# Sheet1.net
KiCad netlist of a schematic drawn in Altium Designer
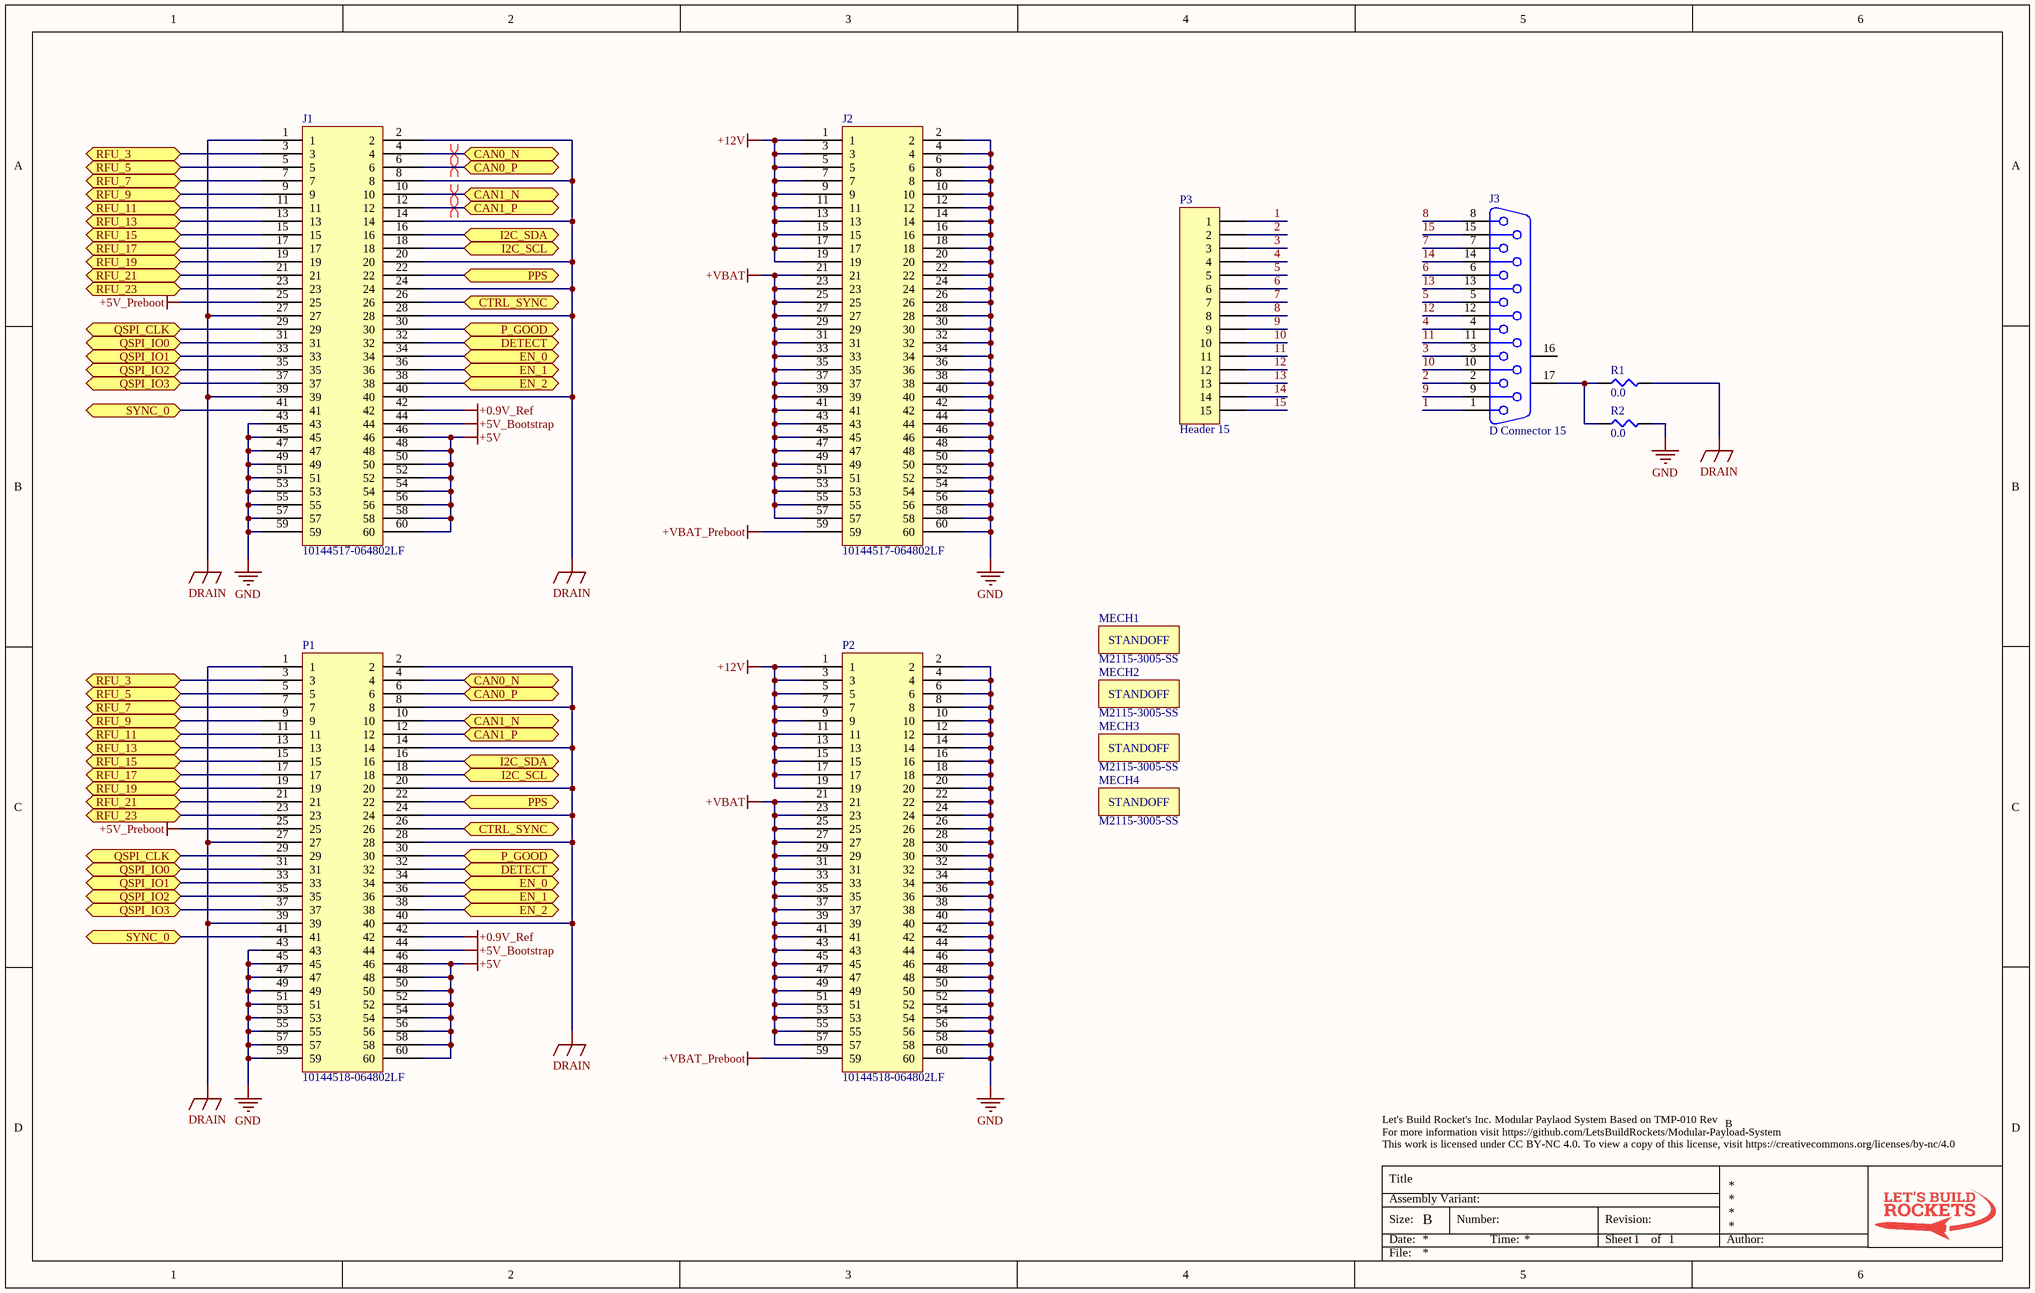
[diagram p0: Sheet1.SchDoc]

(export (version "E")
  (design (tool "Eeschema 10.0.6"))
  (components
    (comp (ref "J1")
      (value "10144517-064802LF")
      (footprint "10144517-064802LF")
      (libsource (lib "ModularPayload") (part "10144517-064802LF"))
    )
    (comp (ref "J2")
      (value "10144517-064802LF")
      (footprint "10144517-064802LF")
      (libsource (lib "ModularPayload") (part "10144517-064802LF"))
    )
    (comp (ref "J3")
      (value "D Connector 15")
      (footprint "DSUB1.385-2H15")
      (description "Receptacle Assembly, 15 Position, Right Angle")
      (fields (field (name "PUBLISHER") "Altium Limited"))
      (libsource (lib "Miscellaneous Connectors") (part "D Connector 15"))
    )
    (comp (ref "MECH1")
      (value "M2115-3005-SS")
      (footprint "M2115-3005-SS")
      (libsource (lib "ModularPayload") (part "M2115-3005-SS"))
    )
    (comp (ref "MECH2")
      (value "M2115-3005-SS")
      (footprint "M2115-3005-SS")
      (libsource (lib "ModularPayload") (part "M2115-3005-SS"))
    )
    (comp (ref "MECH3")
      (value "M2115-3005-SS")
      (footprint "M2115-3005-SS")
      (libsource (lib "ModularPayload") (part "M2115-3005-SS"))
    )
    (comp (ref "MECH4")
      (value "M2115-3005-SS")
      (footprint "M2115-3005-SS")
      (libsource (lib "ModularPayload") (part "M2115-3005-SS"))
    )
    (comp (ref "P1")
      (value "10144518-064802LF")
      (footprint "10144518-064802LF")
      (libsource (lib "ModularPayload") (part "10144518-064802LF"))
    )
    (comp (ref "P2")
      (value "10144518-064802LF")
      (footprint "10144518-064802LF")
      (libsource (lib "ModularPayload") (part "10144518-064802LF"))
    )
    (comp (ref "P3")
      (value "Header 15")
      (footprint "HDR1X15")
      (description "Header, 15-Pin")
      (fields (field (name "PUBLISHER") "Altium Limited"))
      (libsource (lib "Miscellaneous Connectors") (part "Header 15"))
    )
    (comp (ref "R1")
      (value "0.0")
      (footprint "SMD-0402-RES")
      (description "RES SMD 0.0OHM JUMPER 1/10W 0402")
      (fields (field (name "PART NUMBER") "ERJ-2GE0R00X") (field (name "DIGI-KEY PART NUMBER") "P0.0JCT-ND"))
      (libsource (lib "Panasonic_ERJ_0402") (part "ERJ-2GE0R00X"))
    )
    (comp (ref "R2")
      (value "0.0")
      (footprint "SMD-0402-RES")
      (description "RES SMD 0.0OHM JUMPER 1/10W 0402")
      (fields (field (name "PART NUMBER") "ERJ-2GE0R00X") (field (name "DIGI-KEY PART NUMBER") "P0.0JCT-ND"))
      (libsource (lib "Panasonic_ERJ_0402") (part "ERJ-2GE0R00X"))
    )
  )
  (nets
    (net (code "1") (name "+0.9V_Ref") (class "Default")
      (node (ref "J1") (pin "42") (pinfunction "42_42") (pintype "passive"))
      (node (ref "P1") (pin "42") (pinfunction "42_42") (pintype "passive"))
    )
    (net (code "2") (name "+5V") (class "Default")
      (node (ref "J1") (pin "46") (pinfunction "46_46") (pintype "passive"))
      (node (ref "J1") (pin "48") (pinfunction "48_48") (pintype "passive"))
      (node (ref "J1") (pin "50") (pinfunction "50_50") (pintype "passive"))
      (node (ref "J1") (pin "52") (pinfunction "52_52") (pintype "passive"))
      (node (ref "J1") (pin "54") (pinfunction "54_54") (pintype "passive"))
      (node (ref "J1") (pin "56") (pinfunction "56_56") (pintype "passive"))
      (node (ref "J1") (pin "58") (pinfunction "58_58") (pintype "passive"))
      (node (ref "J1") (pin "60") (pinfunction "60_60") (pintype "passive"))
      (node (ref "P1") (pin "46") (pinfunction "46_46") (pintype "passive"))
      (node (ref "P1") (pin "48") (pinfunction "48_48") (pintype "passive"))
      (node (ref "P1") (pin "50") (pinfunction "50_50") (pintype "passive"))
      (node (ref "P1") (pin "52") (pinfunction "52_52") (pintype "passive"))
      (node (ref "P1") (pin "54") (pinfunction "54_54") (pintype "passive"))
      (node (ref "P1") (pin "56") (pinfunction "56_56") (pintype "passive"))
      (node (ref "P1") (pin "58") (pinfunction "58_58") (pintype "passive"))
      (node (ref "P1") (pin "60") (pinfunction "60_60") (pintype "passive"))
    )
    (net (code "3") (name "+5V_Bootstrap") (class "Default")
      (node (ref "J1") (pin "44") (pinfunction "44_44") (pintype "passive"))
      (node (ref "P1") (pin "44") (pinfunction "44_44") (pintype "passive"))
    )
    (net (code "4") (name "+5V_Preboot") (class "Default")
      (node (ref "J1") (pin "25") (pinfunction "25_25") (pintype "passive"))
      (node (ref "P1") (pin "25") (pinfunction "25_25") (pintype "passive"))
    )
    (net (code "5") (name "+12V") (class "Default")
      (node (ref "J2") (pin "1") (pinfunction "1_1") (pintype "passive"))
      (node (ref "J2") (pin "11") (pinfunction "11_11") (pintype "passive"))
      (node (ref "J2") (pin "13") (pinfunction "13_13") (pintype "passive"))
      (node (ref "J2") (pin "15") (pinfunction "15_15") (pintype "passive"))
      (node (ref "J2") (pin "17") (pinfunction "17_17") (pintype "passive"))
      (node (ref "J2") (pin "19") (pinfunction "19_19") (pintype "passive"))
      (node (ref "J2") (pin "3") (pinfunction "3_3") (pintype "passive"))
      (node (ref "J2") (pin "5") (pinfunction "5_5") (pintype "passive"))
      (node (ref "J2") (pin "7") (pinfunction "7_7") (pintype "passive"))
      (node (ref "J2") (pin "9") (pinfunction "9_9") (pintype "passive"))
      (node (ref "P2") (pin "1") (pinfunction "1_1") (pintype "passive"))
      (node (ref "P2") (pin "11") (pinfunction "11_11") (pintype "passive"))
      (node (ref "P2") (pin "13") (pinfunction "13_13") (pintype "passive"))
      (node (ref "P2") (pin "15") (pinfunction "15_15") (pintype "passive"))
      (node (ref "P2") (pin "17") (pinfunction "17_17") (pintype "passive"))
      (node (ref "P2") (pin "19") (pinfunction "19_19") (pintype "passive"))
      (node (ref "P2") (pin "3") (pinfunction "3_3") (pintype "passive"))
      (node (ref "P2") (pin "5") (pinfunction "5_5") (pintype "passive"))
      (node (ref "P2") (pin "7") (pinfunction "7_7") (pintype "passive"))
      (node (ref "P2") (pin "9") (pinfunction "9_9") (pintype "passive"))
    )
    (net (code "6") (name "+VBAT") (class "Default")
      (node (ref "J2") (pin "21") (pinfunction "21_21") (pintype "passive"))
      (node (ref "J2") (pin "23") (pinfunction "23_23") (pintype "passive"))
      (node (ref "J2") (pin "25") (pinfunction "25_25") (pintype "passive"))
      (node (ref "J2") (pin "27") (pinfunction "27_27") (pintype "passive"))
      (node (ref "J2") (pin "29") (pinfunction "29_29") (pintype "passive"))
      (node (ref "J2") (pin "31") (pinfunction "31_31") (pintype "passive"))
      (node (ref "J2") (pin "33") (pinfunction "33_33") (pintype "passive"))
      (node (ref "J2") (pin "35") (pinfunction "35_35") (pintype "passive"))
      (node (ref "J2") (pin "37") (pinfunction "37_37") (pintype "passive"))
      (node (ref "J2") (pin "39") (pinfunction "39_39") (pintype "passive"))
      (node (ref "J2") (pin "41") (pinfunction "41_41") (pintype "passive"))
      (node (ref "J2") (pin "43") (pinfunction "43_43") (pintype "passive"))
      (node (ref "J2") (pin "45") (pinfunction "45_45") (pintype "passive"))
      (node (ref "J2") (pin "47") (pinfunction "47_47") (pintype "passive"))
      (node (ref "J2") (pin "49") (pinfunction "49_49") (pintype "passive"))
      (node (ref "J2") (pin "51") (pinfunction "51_51") (pintype "passive"))
      (node (ref "J2") (pin "53") (pinfunction "53_53") (pintype "passive"))
      (node (ref "J2") (pin "55") (pinfunction "55_55") (pintype "passive"))
      (node (ref "J2") (pin "57") (pinfunction "57_57") (pintype "passive"))
      (node (ref "P2") (pin "21") (pinfunction "21_21") (pintype "passive"))
      (node (ref "P2") (pin "23") (pinfunction "23_23") (pintype "passive"))
      (node (ref "P2") (pin "25") (pinfunction "25_25") (pintype "passive"))
      (node (ref "P2") (pin "27") (pinfunction "27_27") (pintype "passive"))
      (node (ref "P2") (pin "29") (pinfunction "29_29") (pintype "passive"))
      (node (ref "P2") (pin "31") (pinfunction "31_31") (pintype "passive"))
      (node (ref "P2") (pin "33") (pinfunction "33_33") (pintype "passive"))
      (node (ref "P2") (pin "35") (pinfunction "35_35") (pintype "passive"))
      (node (ref "P2") (pin "37") (pinfunction "37_37") (pintype "passive"))
      (node (ref "P2") (pin "39") (pinfunction "39_39") (pintype "passive"))
      (node (ref "P2") (pin "41") (pinfunction "41_41") (pintype "passive"))
      (node (ref "P2") (pin "43") (pinfunction "43_43") (pintype "passive"))
      (node (ref "P2") (pin "45") (pinfunction "45_45") (pintype "passive"))
      (node (ref "P2") (pin "47") (pinfunction "47_47") (pintype "passive"))
      (node (ref "P2") (pin "49") (pinfunction "49_49") (pintype "passive"))
      (node (ref "P2") (pin "51") (pinfunction "51_51") (pintype "passive"))
      (node (ref "P2") (pin "53") (pinfunction "53_53") (pintype "passive"))
      (node (ref "P2") (pin "55") (pinfunction "55_55") (pintype "passive"))
      (node (ref "P2") (pin "57") (pinfunction "57_57") (pintype "passive"))
    )
    (net (code "7") (name "+VBAT_Preboot") (class "Default")
      (node (ref "J2") (pin "59") (pinfunction "59_59") (pintype "passive"))
      (node (ref "P2") (pin "59") (pinfunction "59_59") (pintype "passive"))
    )
    (net (code "8") (name "/1") (class "Default")
      (node (ref "J3") (pin "1") (pinfunction "1_1") (pintype "passive"))
      (node (ref "P3") (pin "1") (pinfunction "1_1") (pintype "passive"))
    )
    (net (code "9") (name "/2") (class "Default")
      (node (ref "J3") (pin "2") (pinfunction "2_2") (pintype "passive"))
      (node (ref "P3") (pin "2") (pinfunction "2_2") (pintype "passive"))
    )
    (net (code "10") (name "/3") (class "Default")
      (node (ref "J3") (pin "3") (pinfunction "3_3") (pintype "passive"))
      (node (ref "P3") (pin "3") (pinfunction "3_3") (pintype "passive"))
    )
    (net (code "11") (name "/4") (class "Default")
      (node (ref "J3") (pin "4") (pinfunction "4_4") (pintype "passive"))
      (node (ref "P3") (pin "4") (pinfunction "4_4") (pintype "passive"))
    )
    (net (code "12") (name "/5") (class "Default")
      (node (ref "J3") (pin "5") (pinfunction "5_5") (pintype "passive"))
      (node (ref "P3") (pin "5") (pinfunction "5_5") (pintype "passive"))
    )
    (net (code "13") (name "/6") (class "Default")
      (node (ref "J3") (pin "6") (pinfunction "6_6") (pintype "passive"))
      (node (ref "P3") (pin "6") (pinfunction "6_6") (pintype "passive"))
    )
    (net (code "14") (name "/7") (class "Default")
      (node (ref "J3") (pin "7") (pinfunction "7_7") (pintype "passive"))
      (node (ref "P3") (pin "7") (pinfunction "7_7") (pintype "passive"))
    )
    (net (code "15") (name "/8") (class "Default")
      (node (ref "J3") (pin "8") (pinfunction "8_8") (pintype "passive"))
      (node (ref "P3") (pin "8") (pinfunction "8_8") (pintype "passive"))
    )
    (net (code "16") (name "/9") (class "Default")
      (node (ref "J3") (pin "9") (pinfunction "9_9") (pintype "passive"))
      (node (ref "P3") (pin "9") (pinfunction "9_9") (pintype "passive"))
    )
    (net (code "17") (name "/10") (class "Default")
      (node (ref "J3") (pin "10") (pinfunction "10_10") (pintype "passive"))
      (node (ref "P3") (pin "10") (pinfunction "10_10") (pintype "passive"))
    )
    (net (code "18") (name "/11") (class "Default")
      (node (ref "J3") (pin "11") (pinfunction "11_11") (pintype "passive"))
      (node (ref "P3") (pin "11") (pinfunction "11_11") (pintype "passive"))
    )
    (net (code "19") (name "/12") (class "Default")
      (node (ref "J3") (pin "12") (pinfunction "12_12") (pintype "passive"))
      (node (ref "P3") (pin "12") (pinfunction "12_12") (pintype "passive"))
    )
    (net (code "20") (name "/13") (class "Default")
      (node (ref "J3") (pin "13") (pinfunction "13_13") (pintype "passive"))
      (node (ref "P3") (pin "13") (pinfunction "13_13") (pintype "passive"))
    )
    (net (code "21") (name "/14") (class "Default")
      (node (ref "J3") (pin "14") (pinfunction "14_14") (pintype "passive"))
      (node (ref "P3") (pin "14") (pinfunction "14_14") (pintype "passive"))
    )
    (net (code "22") (name "/15") (class "Default")
      (node (ref "J3") (pin "15") (pinfunction "15_15") (pintype "passive"))
      (node (ref "P3") (pin "15") (pinfunction "15_15") (pintype "passive"))
    )
    (net (code "23") (name "/CAN0_N") (class "Default")
      (node (ref "J1") (pin "4") (pinfunction "4_4") (pintype "passive"))
      (node (ref "P1") (pin "4") (pinfunction "4_4") (pintype "passive"))
    )
    (net (code "24") (name "/CAN0_P") (class "Default")
      (node (ref "J1") (pin "6") (pinfunction "6_6") (pintype "passive"))
      (node (ref "P1") (pin "6") (pinfunction "6_6") (pintype "passive"))
    )
    (net (code "25") (name "/CAN1_N") (class "Default")
      (node (ref "J1") (pin "10") (pinfunction "10_10") (pintype "passive"))
      (node (ref "P1") (pin "10") (pinfunction "10_10") (pintype "passive"))
    )
    (net (code "26") (name "/CAN1_P") (class "Default")
      (node (ref "J1") (pin "12") (pinfunction "12_12") (pintype "passive"))
      (node (ref "P1") (pin "12") (pinfunction "12_12") (pintype "passive"))
    )
    (net (code "27") (name "/CTRL_SYNC") (class "Default")
      (node (ref "J1") (pin "26") (pinfunction "26_26") (pintype "passive"))
      (node (ref "P1") (pin "26") (pinfunction "26_26") (pintype "passive"))
    )
    (net (code "28") (name "/DETECT") (class "Default")
      (node (ref "J1") (pin "32") (pinfunction "32_32") (pintype "passive"))
      (node (ref "P1") (pin "32") (pinfunction "32_32") (pintype "passive"))
    )
    (net (code "29") (name "/EN_0") (class "Default")
      (node (ref "J1") (pin "34") (pinfunction "34_34") (pintype "passive"))
      (node (ref "P1") (pin "34") (pinfunction "34_34") (pintype "passive"))
    )
    (net (code "30") (name "/EN_1") (class "Default")
      (node (ref "J1") (pin "36") (pinfunction "36_36") (pintype "passive"))
      (node (ref "P1") (pin "36") (pinfunction "36_36") (pintype "passive"))
    )
    (net (code "31") (name "/EN_2") (class "Default")
      (node (ref "J1") (pin "38") (pinfunction "38_38") (pintype "passive"))
      (node (ref "P1") (pin "38") (pinfunction "38_38") (pintype "passive"))
    )
    (net (code "32") (name "/I2C_SCL") (class "Default")
      (node (ref "J1") (pin "18") (pinfunction "18_18") (pintype "passive"))
      (node (ref "P1") (pin "18") (pinfunction "18_18") (pintype "passive"))
    )
    (net (code "33") (name "/I2C_SDA") (class "Default")
      (node (ref "J1") (pin "16") (pinfunction "16_16") (pintype "passive"))
      (node (ref "P1") (pin "16") (pinfunction "16_16") (pintype "passive"))
    )
    (net (code "34") (name "/PPS") (class "Default")
      (node (ref "J1") (pin "22") (pinfunction "22_22") (pintype "passive"))
      (node (ref "P1") (pin "22") (pinfunction "22_22") (pintype "passive"))
    )
    (net (code "35") (name "/P_GOOD") (class "Default")
      (node (ref "J1") (pin "30") (pinfunction "30_30") (pintype "passive"))
      (node (ref "P1") (pin "30") (pinfunction "30_30") (pintype "passive"))
    )
    (net (code "36") (name "/QSPI_CLK") (class "Default")
      (node (ref "J1") (pin "29") (pinfunction "29_29") (pintype "passive"))
      (node (ref "P1") (pin "29") (pinfunction "29_29") (pintype "passive"))
    )
    (net (code "37") (name "/QSPI_IO0") (class "Default")
      (node (ref "J1") (pin "31") (pinfunction "31_31") (pintype "passive"))
      (node (ref "P1") (pin "31") (pinfunction "31_31") (pintype "passive"))
    )
    (net (code "38") (name "/QSPI_IO1") (class "Default")
      (node (ref "J1") (pin "33") (pinfunction "33_33") (pintype "passive"))
      (node (ref "P1") (pin "33") (pinfunction "33_33") (pintype "passive"))
    )
    (net (code "39") (name "/QSPI_IO2") (class "Default")
      (node (ref "J1") (pin "35") (pinfunction "35_35") (pintype "passive"))
      (node (ref "P1") (pin "35") (pinfunction "35_35") (pintype "passive"))
    )
    (net (code "40") (name "/QSPI_IO3") (class "Default")
      (node (ref "J1") (pin "37") (pinfunction "37_37") (pintype "passive"))
      (node (ref "P1") (pin "37") (pinfunction "37_37") (pintype "passive"))
    )
    (net (code "41") (name "/RFU_3") (class "Default")
      (node (ref "J1") (pin "3") (pinfunction "3_3") (pintype "passive"))
      (node (ref "P1") (pin "3") (pinfunction "3_3") (pintype "passive"))
    )
    (net (code "42") (name "/RFU_5") (class "Default")
      (node (ref "J1") (pin "5") (pinfunction "5_5") (pintype "passive"))
      (node (ref "P1") (pin "5") (pinfunction "5_5") (pintype "passive"))
    )
    (net (code "43") (name "/RFU_7") (class "Default")
      (node (ref "J1") (pin "7") (pinfunction "7_7") (pintype "passive"))
      (node (ref "P1") (pin "7") (pinfunction "7_7") (pintype "passive"))
    )
    (net (code "44") (name "/RFU_9") (class "Default")
      (node (ref "J1") (pin "9") (pinfunction "9_9") (pintype "passive"))
      (node (ref "P1") (pin "9") (pinfunction "9_9") (pintype "passive"))
    )
    (net (code "45") (name "/RFU_11") (class "Default")
      (node (ref "J1") (pin "11") (pinfunction "11_11") (pintype "passive"))
      (node (ref "P1") (pin "11") (pinfunction "11_11") (pintype "passive"))
    )
    (net (code "46") (name "/RFU_13") (class "Default")
      (node (ref "J1") (pin "13") (pinfunction "13_13") (pintype "passive"))
      (node (ref "P1") (pin "13") (pinfunction "13_13") (pintype "passive"))
    )
    (net (code "47") (name "/RFU_15") (class "Default")
      (node (ref "J1") (pin "15") (pinfunction "15_15") (pintype "passive"))
      (node (ref "P1") (pin "15") (pinfunction "15_15") (pintype "passive"))
    )
    (net (code "48") (name "/RFU_17") (class "Default")
      (node (ref "J1") (pin "17") (pinfunction "17_17") (pintype "passive"))
      (node (ref "P1") (pin "17") (pinfunction "17_17") (pintype "passive"))
    )
    (net (code "49") (name "/RFU_19") (class "Default")
      (node (ref "J1") (pin "19") (pinfunction "19_19") (pintype "passive"))
      (node (ref "P1") (pin "19") (pinfunction "19_19") (pintype "passive"))
    )
    (net (code "50") (name "/RFU_21") (class "Default")
      (node (ref "J1") (pin "21") (pinfunction "21_21") (pintype "passive"))
      (node (ref "P1") (pin "21") (pinfunction "21_21") (pintype "passive"))
    )
    (net (code "51") (name "/RFU_23") (class "Default")
      (node (ref "J1") (pin "23") (pinfunction "23_23") (pintype "passive"))
      (node (ref "P1") (pin "23") (pinfunction "23_23") (pintype "passive"))
    )
    (net (code "52") (name "/SYNC_0") (class "Default")
      (node (ref "J1") (pin "41") (pinfunction "41_41") (pintype "passive"))
      (node (ref "P1") (pin "41") (pinfunction "41_41") (pintype "passive"))
    )
    (net (code "53") (name "DRAIN") (class "Default")
      (node (ref "J1") (pin "1") (pinfunction "1_1") (pintype "passive"))
      (node (ref "J1") (pin "14") (pinfunction "14_14") (pintype "passive"))
      (node (ref "J1") (pin "2") (pinfunction "2_2") (pintype "passive"))
      (node (ref "J1") (pin "20") (pinfunction "20_20") (pintype "passive"))
      (node (ref "J1") (pin "24") (pinfunction "24_24") (pintype "passive"))
      (node (ref "J1") (pin "27") (pinfunction "27_27") (pintype "passive"))
      (node (ref "J1") (pin "28") (pinfunction "28_28") (pintype "passive"))
      (node (ref "J1") (pin "39") (pinfunction "39_39") (pintype "passive"))
      (node (ref "J1") (pin "40") (pinfunction "40_40") (pintype "passive"))
      (node (ref "J1") (pin "8") (pinfunction "8_8") (pintype "passive"))
      (node (ref "P1") (pin "1") (pinfunction "1_1") (pintype "passive"))
      (node (ref "P1") (pin "14") (pinfunction "14_14") (pintype "passive"))
      (node (ref "P1") (pin "2") (pinfunction "2_2") (pintype "passive"))
      (node (ref "P1") (pin "20") (pinfunction "20_20") (pintype "passive"))
      (node (ref "P1") (pin "24") (pinfunction "24_24") (pintype "passive"))
      (node (ref "P1") (pin "27") (pinfunction "27_27") (pintype "passive"))
      (node (ref "P1") (pin "28") (pinfunction "28_28") (pintype "passive"))
      (node (ref "P1") (pin "39") (pinfunction "39_39") (pintype "passive"))
      (node (ref "P1") (pin "40") (pinfunction "40_40") (pintype "passive"))
      (node (ref "P1") (pin "8") (pinfunction "8_8") (pintype "passive"))
      (node (ref "R1") (pin "2") (pinfunction "2_2") (pintype "passive"))
    )
    (net (code "54") (name "GND") (class "Default")
      (node (ref "J1") (pin "43") (pinfunction "43_43") (pintype "passive"))
      (node (ref "J1") (pin "45") (pinfunction "45_45") (pintype "passive"))
      (node (ref "J1") (pin "47") (pinfunction "47_47") (pintype "passive"))
      (node (ref "J1") (pin "49") (pinfunction "49_49") (pintype "passive"))
      (node (ref "J1") (pin "51") (pinfunction "51_51") (pintype "passive"))
      (node (ref "J1") (pin "53") (pinfunction "53_53") (pintype "passive"))
      (node (ref "J1") (pin "55") (pinfunction "55_55") (pintype "passive"))
      (node (ref "J1") (pin "57") (pinfunction "57_57") (pintype "passive"))
      (node (ref "J1") (pin "59") (pinfunction "59_59") (pintype "passive"))
      (node (ref "J2") (pin "10") (pinfunction "10_10") (pintype "passive"))
      (node (ref "J2") (pin "12") (pinfunction "12_12") (pintype "passive"))
      (node (ref "J2") (pin "14") (pinfunction "14_14") (pintype "passive"))
      (node (ref "J2") (pin "16") (pinfunction "16_16") (pintype "passive"))
      (node (ref "J2") (pin "18") (pinfunction "18_18") (pintype "passive"))
      (node (ref "J2") (pin "2") (pinfunction "2_2") (pintype "passive"))
      (node (ref "J2") (pin "20") (pinfunction "20_20") (pintype "passive"))
      (node (ref "J2") (pin "22") (pinfunction "22_22") (pintype "passive"))
      (node (ref "J2") (pin "24") (pinfunction "24_24") (pintype "passive"))
      (node (ref "J2") (pin "26") (pinfunction "26_26") (pintype "passive"))
      (node (ref "J2") (pin "28") (pinfunction "28_28") (pintype "passive"))
      (node (ref "J2") (pin "30") (pinfunction "30_30") (pintype "passive"))
      (node (ref "J2") (pin "32") (pinfunction "32_32") (pintype "passive"))
      (node (ref "J2") (pin "34") (pinfunction "34_34") (pintype "passive"))
      (node (ref "J2") (pin "36") (pinfunction "36_36") (pintype "passive"))
      (node (ref "J2") (pin "38") (pinfunction "38_38") (pintype "passive"))
      (node (ref "J2") (pin "4") (pinfunction "4_4") (pintype "passive"))
      (node (ref "J2") (pin "40") (pinfunction "40_40") (pintype "passive"))
      (node (ref "J2") (pin "42") (pinfunction "42_42") (pintype "passive"))
      (node (ref "J2") (pin "44") (pinfunction "44_44") (pintype "passive"))
      (node (ref "J2") (pin "46") (pinfunction "46_46") (pintype "passive"))
      (node (ref "J2") (pin "48") (pinfunction "48_48") (pintype "passive"))
      (node (ref "J2") (pin "50") (pinfunction "50_50") (pintype "passive"))
      (node (ref "J2") (pin "52") (pinfunction "52_52") (pintype "passive"))
      (node (ref "J2") (pin "54") (pinfunction "54_54") (pintype "passive"))
      (node (ref "J2") (pin "56") (pinfunction "56_56") (pintype "passive"))
      (node (ref "J2") (pin "58") (pinfunction "58_58") (pintype "passive"))
      (node (ref "J2") (pin "6") (pinfunction "6_6") (pintype "passive"))
      (node (ref "J2") (pin "60") (pinfunction "60_60") (pintype "passive"))
      (node (ref "J2") (pin "8") (pinfunction "8_8") (pintype "passive"))
      (node (ref "P1") (pin "43") (pinfunction "43_43") (pintype "passive"))
      (node (ref "P1") (pin "45") (pinfunction "45_45") (pintype "passive"))
      (node (ref "P1") (pin "47") (pinfunction "47_47") (pintype "passive"))
      (node (ref "P1") (pin "49") (pinfunction "49_49") (pintype "passive"))
      (node (ref "P1") (pin "51") (pinfunction "51_51") (pintype "passive"))
      (node (ref "P1") (pin "53") (pinfunction "53_53") (pintype "passive"))
      (node (ref "P1") (pin "55") (pinfunction "55_55") (pintype "passive"))
      (node (ref "P1") (pin "57") (pinfunction "57_57") (pintype "passive"))
      (node (ref "P1") (pin "59") (pinfunction "59_59") (pintype "passive"))
      (node (ref "P2") (pin "10") (pinfunction "10_10") (pintype "passive"))
      (node (ref "P2") (pin "12") (pinfunction "12_12") (pintype "passive"))
      (node (ref "P2") (pin "14") (pinfunction "14_14") (pintype "passive"))
      (node (ref "P2") (pin "16") (pinfunction "16_16") (pintype "passive"))
      (node (ref "P2") (pin "18") (pinfunction "18_18") (pintype "passive"))
      (node (ref "P2") (pin "2") (pinfunction "2_2") (pintype "passive"))
      (node (ref "P2") (pin "20") (pinfunction "20_20") (pintype "passive"))
      (node (ref "P2") (pin "22") (pinfunction "22_22") (pintype "passive"))
      (node (ref "P2") (pin "24") (pinfunction "24_24") (pintype "passive"))
      (node (ref "P2") (pin "26") (pinfunction "26_26") (pintype "passive"))
      (node (ref "P2") (pin "28") (pinfunction "28_28") (pintype "passive"))
      (node (ref "P2") (pin "30") (pinfunction "30_30") (pintype "passive"))
      (node (ref "P2") (pin "32") (pinfunction "32_32") (pintype "passive"))
      (node (ref "P2") (pin "34") (pinfunction "34_34") (pintype "passive"))
      (node (ref "P2") (pin "36") (pinfunction "36_36") (pintype "passive"))
      (node (ref "P2") (pin "38") (pinfunction "38_38") (pintype "passive"))
      (node (ref "P2") (pin "4") (pinfunction "4_4") (pintype "passive"))
      (node (ref "P2") (pin "40") (pinfunction "40_40") (pintype "passive"))
      (node (ref "P2") (pin "42") (pinfunction "42_42") (pintype "passive"))
      (node (ref "P2") (pin "44") (pinfunction "44_44") (pintype "passive"))
      (node (ref "P2") (pin "46") (pinfunction "46_46") (pintype "passive"))
      (node (ref "P2") (pin "48") (pinfunction "48_48") (pintype "passive"))
      (node (ref "P2") (pin "50") (pinfunction "50_50") (pintype "passive"))
      (node (ref "P2") (pin "52") (pinfunction "52_52") (pintype "passive"))
      (node (ref "P2") (pin "54") (pinfunction "54_54") (pintype "passive"))
      (node (ref "P2") (pin "56") (pinfunction "56_56") (pintype "passive"))
      (node (ref "P2") (pin "58") (pinfunction "58_58") (pintype "passive"))
      (node (ref "P2") (pin "6") (pinfunction "6_6") (pintype "passive"))
      (node (ref "P2") (pin "60") (pinfunction "60_60") (pintype "passive"))
      (node (ref "P2") (pin "8") (pinfunction "8_8") (pintype "passive"))
      (node (ref "R2") (pin "2") (pinfunction "2_2") (pintype "passive"))
    )
    (net (code "55") (name "Net-(J3-MH2)") (class "Default")
      (node (ref "J3") (pin "17") (pinfunction "MH2_17") (pintype "passive"))
      (node (ref "R1") (pin "1") (pinfunction "1_1") (pintype "passive"))
      (node (ref "R2") (pin "1") (pinfunction "1_1") (pintype "passive"))
    )
    (net (code "56") (name "unconnected-(J3-MH1-Pad16)") (class "Default")
      (node (ref "J3") (pin "16") (pinfunction "MH1_16") (pintype "passive"))
    )
  )
)
